# Parallel_Capacitor.net
KiCad netlist of a schematic drawn in Altium Designer
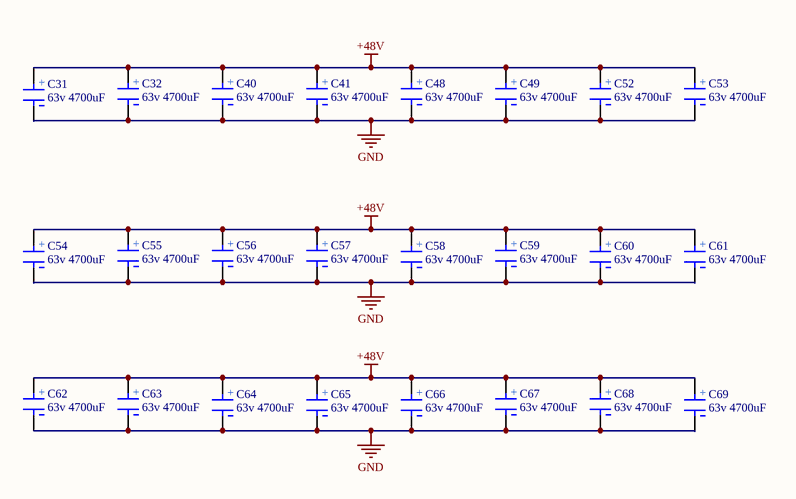
[diagram p0: Parallel_Capacitor.SchDoc]

(export (version "E")
  (design (tool "Eeschema 10.0.6"))
  (components
    (comp (ref "C31")
      (value "63v 4700uF")
      (footprint "cap 10*20")
      (description "PKL5-063V472MM450 Aluminum Electrolytic Capacitors - Snap In 63volts 4700uF 20%")
      (fields
        (field (name "MANUFACTURER") "Nichicon")
        (field (name "MANUFACTURER PART NUMBER") "LKS1J472MESZ")
      )
      (libsource (lib "PROJE") (part "capacitor 10*20"))
    )
    (comp (ref "C32")
      (value "63v 4700uF")
      (footprint "cap 10*20")
      (description "PKL5-063V472MM450 Aluminum Electrolytic Capacitors - Snap In 63volts 4700uF 20%")
      (fields
        (field (name "MANUFACTURER") "Nichicon")
        (field (name "MANUFACTURER PART NUMBER") "LKS1J472MESZ")
      )
      (libsource (lib "PROJE") (part "capacitor 10*20"))
    )
    (comp (ref "C40")
      (value "63v 4700uF")
      (footprint "cap 10*20")
      (description "PKL5-063V472MM450 Aluminum Electrolytic Capacitors - Snap In 63volts 4700uF 20%")
      (fields
        (field (name "MANUFACTURER") "Nichicon")
        (field (name "MANUFACTURER PART NUMBER") "LKS1J472MESZ")
      )
      (libsource (lib "PROJE") (part "capacitor 10*20"))
    )
    (comp (ref "C41")
      (value "63v 4700uF")
      (footprint "cap 10*20")
      (description "PKL5-063V472MM450 Aluminum Electrolytic Capacitors - Snap In 63volts 4700uF 20%")
      (fields
        (field (name "MANUFACTURER") "Nichicon")
        (field (name "MANUFACTURER PART NUMBER") "LKS1J472MESZ")
      )
      (libsource (lib "PROJE") (part "capacitor 10*20"))
    )
    (comp (ref "C48")
      (value "63v 4700uF")
      (footprint "cap 10*20")
      (description "PKL5-063V472MM450 Aluminum Electrolytic Capacitors - Snap In 63volts 4700uF 20%")
      (fields
        (field (name "MANUFACTURER") "Nichicon")
        (field (name "MANUFACTURER PART NUMBER") "LKS1J472MESZ")
      )
      (libsource (lib "PROJE") (part "capacitor 10*20"))
    )
    (comp (ref "C49")
      (value "63v 4700uF")
      (footprint "cap 10*20")
      (description "PKL5-063V472MM450 Aluminum Electrolytic Capacitors - Snap In 63volts 4700uF 20%")
      (fields
        (field (name "MANUFACTURER") "Nichicon")
        (field (name "MANUFACTURER PART NUMBER") "LKS1J472MESZ")
      )
      (libsource (lib "PROJE") (part "capacitor 10*20"))
    )
    (comp (ref "C52")
      (value "63v 4700uF")
      (footprint "cap 10*20")
      (description "PKL5-063V472MM450 Aluminum Electrolytic Capacitors - Snap In 63volts 4700uF 20%")
      (fields
        (field (name "MANUFACTURER") "Nichicon")
        (field (name "MANUFACTURER PART NUMBER") "LKS1J472MESZ")
      )
      (libsource (lib "PROJE") (part "capacitor 10*20"))
    )
    (comp (ref "C53")
      (value "63v 4700uF")
      (footprint "cap 10*20")
      (description "PKL5-063V472MM450 Aluminum Electrolytic Capacitors - Snap In 63volts 4700uF 20%")
      (fields
        (field (name "MANUFACTURER") "Nichicon")
        (field (name "MANUFACTURER PART NUMBER") "LKS1J472MESZ")
      )
      (libsource (lib "PROJE") (part "capacitor 10*20"))
    )
    (comp (ref "C54")
      (value "63v 4700uF")
      (footprint "cap 10*20")
      (description "PKL5-063V472MM450 Aluminum Electrolytic Capacitors - Snap In 63volts 4700uF 20%")
      (fields
        (field (name "MANUFACTURER") "Nichicon")
        (field (name "MANUFACTURER PART NUMBER") "LKS1J472MESZ")
      )
      (libsource (lib "PROJE") (part "capacitor 10*20"))
    )
    (comp (ref "C55")
      (value "63v 4700uF")
      (footprint "cap 10*20")
      (description "PKL5-063V472MM450 Aluminum Electrolytic Capacitors - Snap In 63volts 4700uF 20%")
      (fields
        (field (name "MANUFACTURER") "Nichicon")
        (field (name "MANUFACTURER PART NUMBER") "LKS1J472MESZ")
      )
      (libsource (lib "PROJE") (part "capacitor 10*20"))
    )
    (comp (ref "C56")
      (value "63v 4700uF")
      (footprint "cap 10*20")
      (description "PKL5-063V472MM450 Aluminum Electrolytic Capacitors - Snap In 63volts 4700uF 20%")
      (fields
        (field (name "MANUFACTURER") "Nichicon")
        (field (name "MANUFACTURER PART NUMBER") "LKS1J472MESZ")
      )
      (libsource (lib "PROJE") (part "capacitor 10*20"))
    )
    (comp (ref "C57")
      (value "63v 4700uF")
      (footprint "cap 10*20")
      (description "PKL5-063V472MM450 Aluminum Electrolytic Capacitors - Snap In 63volts 4700uF 20%")
      (fields
        (field (name "MANUFACTURER") "Nichicon")
        (field (name "MANUFACTURER PART NUMBER") "LKS1J472MESZ")
      )
      (libsource (lib "PROJE") (part "capacitor 10*20"))
    )
    (comp (ref "C58")
      (value "63v 4700uF")
      (footprint "cap 10*20")
      (description "PKL5-063V472MM450 Aluminum Electrolytic Capacitors - Snap In 63volts 4700uF 20%")
      (fields
        (field (name "MANUFACTURER") "Nichicon")
        (field (name "MANUFACTURER PART NUMBER") "LKS1J472MESZ")
      )
      (libsource (lib "PROJE") (part "capacitor 10*20"))
    )
    (comp (ref "C59")
      (value "63v 4700uF")
      (footprint "cap 10*20")
      (description "PKL5-063V472MM450 Aluminum Electrolytic Capacitors - Snap In 63volts 4700uF 20%")
      (fields
        (field (name "MANUFACTURER") "Nichicon")
        (field (name "MANUFACTURER PART NUMBER") "LKS1J472MESZ")
      )
      (libsource (lib "PROJE") (part "capacitor 10*20"))
    )
    (comp (ref "C60")
      (value "63v 4700uF")
      (footprint "cap 10*20")
      (description "PKL5-063V472MM450 Aluminum Electrolytic Capacitors - Snap In 63volts 4700uF 20%")
      (fields
        (field (name "MANUFACTURER") "Nichicon")
        (field (name "MANUFACTURER PART NUMBER") "LKS1J472MESZ")
      )
      (libsource (lib "PROJE") (part "capacitor 10*20"))
    )
    (comp (ref "C61")
      (value "63v 4700uF")
      (footprint "cap 10*20")
      (description "PKL5-063V472MM450 Aluminum Electrolytic Capacitors - Snap In 63volts 4700uF 20%")
      (fields
        (field (name "MANUFACTURER") "Nichicon")
        (field (name "MANUFACTURER PART NUMBER") "LKS1J472MESZ")
      )
      (libsource (lib "PROJE") (part "capacitor 10*20"))
    )
    (comp (ref "C62")
      (value "63v 4700uF")
      (footprint "cap 10*20")
      (description "PKL5-063V472MM450 Aluminum Electrolytic Capacitors - Snap In 63volts 4700uF 20%")
      (fields
        (field (name "MANUFACTURER") "Nichicon")
        (field (name "MANUFACTURER PART NUMBER") "LKS1J472MESZ")
      )
      (libsource (lib "PROJE") (part "capacitor 10*20"))
    )
    (comp (ref "C63")
      (value "63v 4700uF")
      (footprint "cap 10*20")
      (description "PKL5-063V472MM450 Aluminum Electrolytic Capacitors - Snap In 63volts 4700uF 20%")
      (fields
        (field (name "MANUFACTURER") "Nichicon")
        (field (name "MANUFACTURER PART NUMBER") "LKS1J472MESZ")
      )
      (libsource (lib "PROJE") (part "capacitor 10*20"))
    )
    (comp (ref "C64")
      (value "63v 4700uF")
      (footprint "cap 10*20")
      (description "PKL5-063V472MM450 Aluminum Electrolytic Capacitors - Snap In 63volts 4700uF 20%")
      (fields
        (field (name "MANUFACTURER") "Nichicon")
        (field (name "MANUFACTURER PART NUMBER") "LKS1J472MESZ")
      )
      (libsource (lib "PROJE") (part "capacitor 10*20"))
    )
    (comp (ref "C65")
      (value "63v 4700uF")
      (footprint "cap 10*20")
      (description "PKL5-063V472MM450 Aluminum Electrolytic Capacitors - Snap In 63volts 4700uF 20%")
      (fields
        (field (name "MANUFACTURER") "Nichicon")
        (field (name "MANUFACTURER PART NUMBER") "LKS1J472MESZ")
      )
      (libsource (lib "PROJE") (part "capacitor 10*20"))
    )
    (comp (ref "C66")
      (value "63v 4700uF")
      (footprint "cap 10*20")
      (description "PKL5-063V472MM450 Aluminum Electrolytic Capacitors - Snap In 63volts 4700uF 20%")
      (fields
        (field (name "MANUFACTURER") "Nichicon")
        (field (name "MANUFACTURER PART NUMBER") "LKS1J472MESZ")
      )
      (libsource (lib "PROJE") (part "capacitor 10*20"))
    )
    (comp (ref "C67")
      (value "63v 4700uF")
      (footprint "cap 10*20")
      (description "PKL5-063V472MM450 Aluminum Electrolytic Capacitors - Snap In 63volts 4700uF 20%")
      (fields
        (field (name "MANUFACTURER") "Nichicon")
        (field (name "MANUFACTURER PART NUMBER") "LKS1J472MESZ")
      )
      (libsource (lib "PROJE") (part "capacitor 10*20"))
    )
    (comp (ref "C68")
      (value "63v 4700uF")
      (footprint "cap 10*20")
      (description "PKL5-063V472MM450 Aluminum Electrolytic Capacitors - Snap In 63volts 4700uF 20%")
      (fields
        (field (name "MANUFACTURER") "Nichicon")
        (field (name "MANUFACTURER PART NUMBER") "LKS1J472MESZ")
      )
      (libsource (lib "PROJE") (part "capacitor 10*20"))
    )
    (comp (ref "C69")
      (value "63v 4700uF")
      (footprint "cap 10*20")
      (description "PKL5-063V472MM450 Aluminum Electrolytic Capacitors - Snap In 63volts 4700uF 20%")
      (fields
        (field (name "MANUFACTURER") "Nichicon")
        (field (name "MANUFACTURER PART NUMBER") "LKS1J472MESZ")
      )
      (libsource (lib "PROJE") (part "capacitor 10*20"))
    )
  )
  (nets
    (net (code "1") (name "+48V") (class "Default")
      (node (ref "C31") (pin "1") (pinfunction "1_1") (pintype "passive"))
      (node (ref "C32") (pin "1") (pinfunction "1_1") (pintype "passive"))
      (node (ref "C40") (pin "1") (pinfunction "1_1") (pintype "passive"))
      (node (ref "C41") (pin "1") (pinfunction "1_1") (pintype "passive"))
      (node (ref "C48") (pin "1") (pinfunction "1_1") (pintype "passive"))
      (node (ref "C49") (pin "1") (pinfunction "1_1") (pintype "passive"))
      (node (ref "C52") (pin "1") (pinfunction "1_1") (pintype "passive"))
      (node (ref "C53") (pin "1") (pinfunction "1_1") (pintype "passive"))
      (node (ref "C54") (pin "1") (pinfunction "1_1") (pintype "passive"))
      (node (ref "C55") (pin "1") (pinfunction "1_1") (pintype "passive"))
      (node (ref "C56") (pin "1") (pinfunction "1_1") (pintype "passive"))
      (node (ref "C57") (pin "1") (pinfunction "1_1") (pintype "passive"))
      (node (ref "C58") (pin "1") (pinfunction "1_1") (pintype "passive"))
      (node (ref "C59") (pin "1") (pinfunction "1_1") (pintype "passive"))
      (node (ref "C60") (pin "1") (pinfunction "1_1") (pintype "passive"))
      (node (ref "C61") (pin "1") (pinfunction "1_1") (pintype "passive"))
      (node (ref "C62") (pin "1") (pinfunction "1_1") (pintype "passive"))
      (node (ref "C63") (pin "1") (pinfunction "1_1") (pintype "passive"))
      (node (ref "C64") (pin "1") (pinfunction "1_1") (pintype "passive"))
      (node (ref "C65") (pin "1") (pinfunction "1_1") (pintype "passive"))
      (node (ref "C66") (pin "1") (pinfunction "1_1") (pintype "passive"))
      (node (ref "C67") (pin "1") (pinfunction "1_1") (pintype "passive"))
      (node (ref "C68") (pin "1") (pinfunction "1_1") (pintype "passive"))
      (node (ref "C69") (pin "1") (pinfunction "1_1") (pintype "passive"))
    )
    (net (code "2") (name "GND") (class "Default")
      (node (ref "C31") (pin "2") (pinfunction "2_2") (pintype "passive"))
      (node (ref "C32") (pin "2") (pinfunction "2_2") (pintype "passive"))
      (node (ref "C40") (pin "2") (pinfunction "2_2") (pintype "passive"))
      (node (ref "C41") (pin "2") (pinfunction "2_2") (pintype "passive"))
      (node (ref "C48") (pin "2") (pinfunction "2_2") (pintype "passive"))
      (node (ref "C49") (pin "2") (pinfunction "2_2") (pintype "passive"))
      (node (ref "C52") (pin "2") (pinfunction "2_2") (pintype "passive"))
      (node (ref "C53") (pin "2") (pinfunction "2_2") (pintype "passive"))
      (node (ref "C54") (pin "2") (pinfunction "2_2") (pintype "passive"))
      (node (ref "C55") (pin "2") (pinfunction "2_2") (pintype "passive"))
      (node (ref "C56") (pin "2") (pinfunction "2_2") (pintype "passive"))
      (node (ref "C57") (pin "2") (pinfunction "2_2") (pintype "passive"))
      (node (ref "C58") (pin "2") (pinfunction "2_2") (pintype "passive"))
      (node (ref "C59") (pin "2") (pinfunction "2_2") (pintype "passive"))
      (node (ref "C60") (pin "2") (pinfunction "2_2") (pintype "passive"))
      (node (ref "C61") (pin "2") (pinfunction "2_2") (pintype "passive"))
      (node (ref "C62") (pin "2") (pinfunction "2_2") (pintype "passive"))
      (node (ref "C63") (pin "2") (pinfunction "2_2") (pintype "passive"))
      (node (ref "C64") (pin "2") (pinfunction "2_2") (pintype "passive"))
      (node (ref "C65") (pin "2") (pinfunction "2_2") (pintype "passive"))
      (node (ref "C66") (pin "2") (pinfunction "2_2") (pintype "passive"))
      (node (ref "C67") (pin "2") (pinfunction "2_2") (pintype "passive"))
      (node (ref "C68") (pin "2") (pinfunction "2_2") (pintype "passive"))
      (node (ref "C69") (pin "2") (pinfunction "2_2") (pintype "passive"))
    )
  )
)
